# B3606.net
KiCad netlist of a schematic drawn in EAGLE
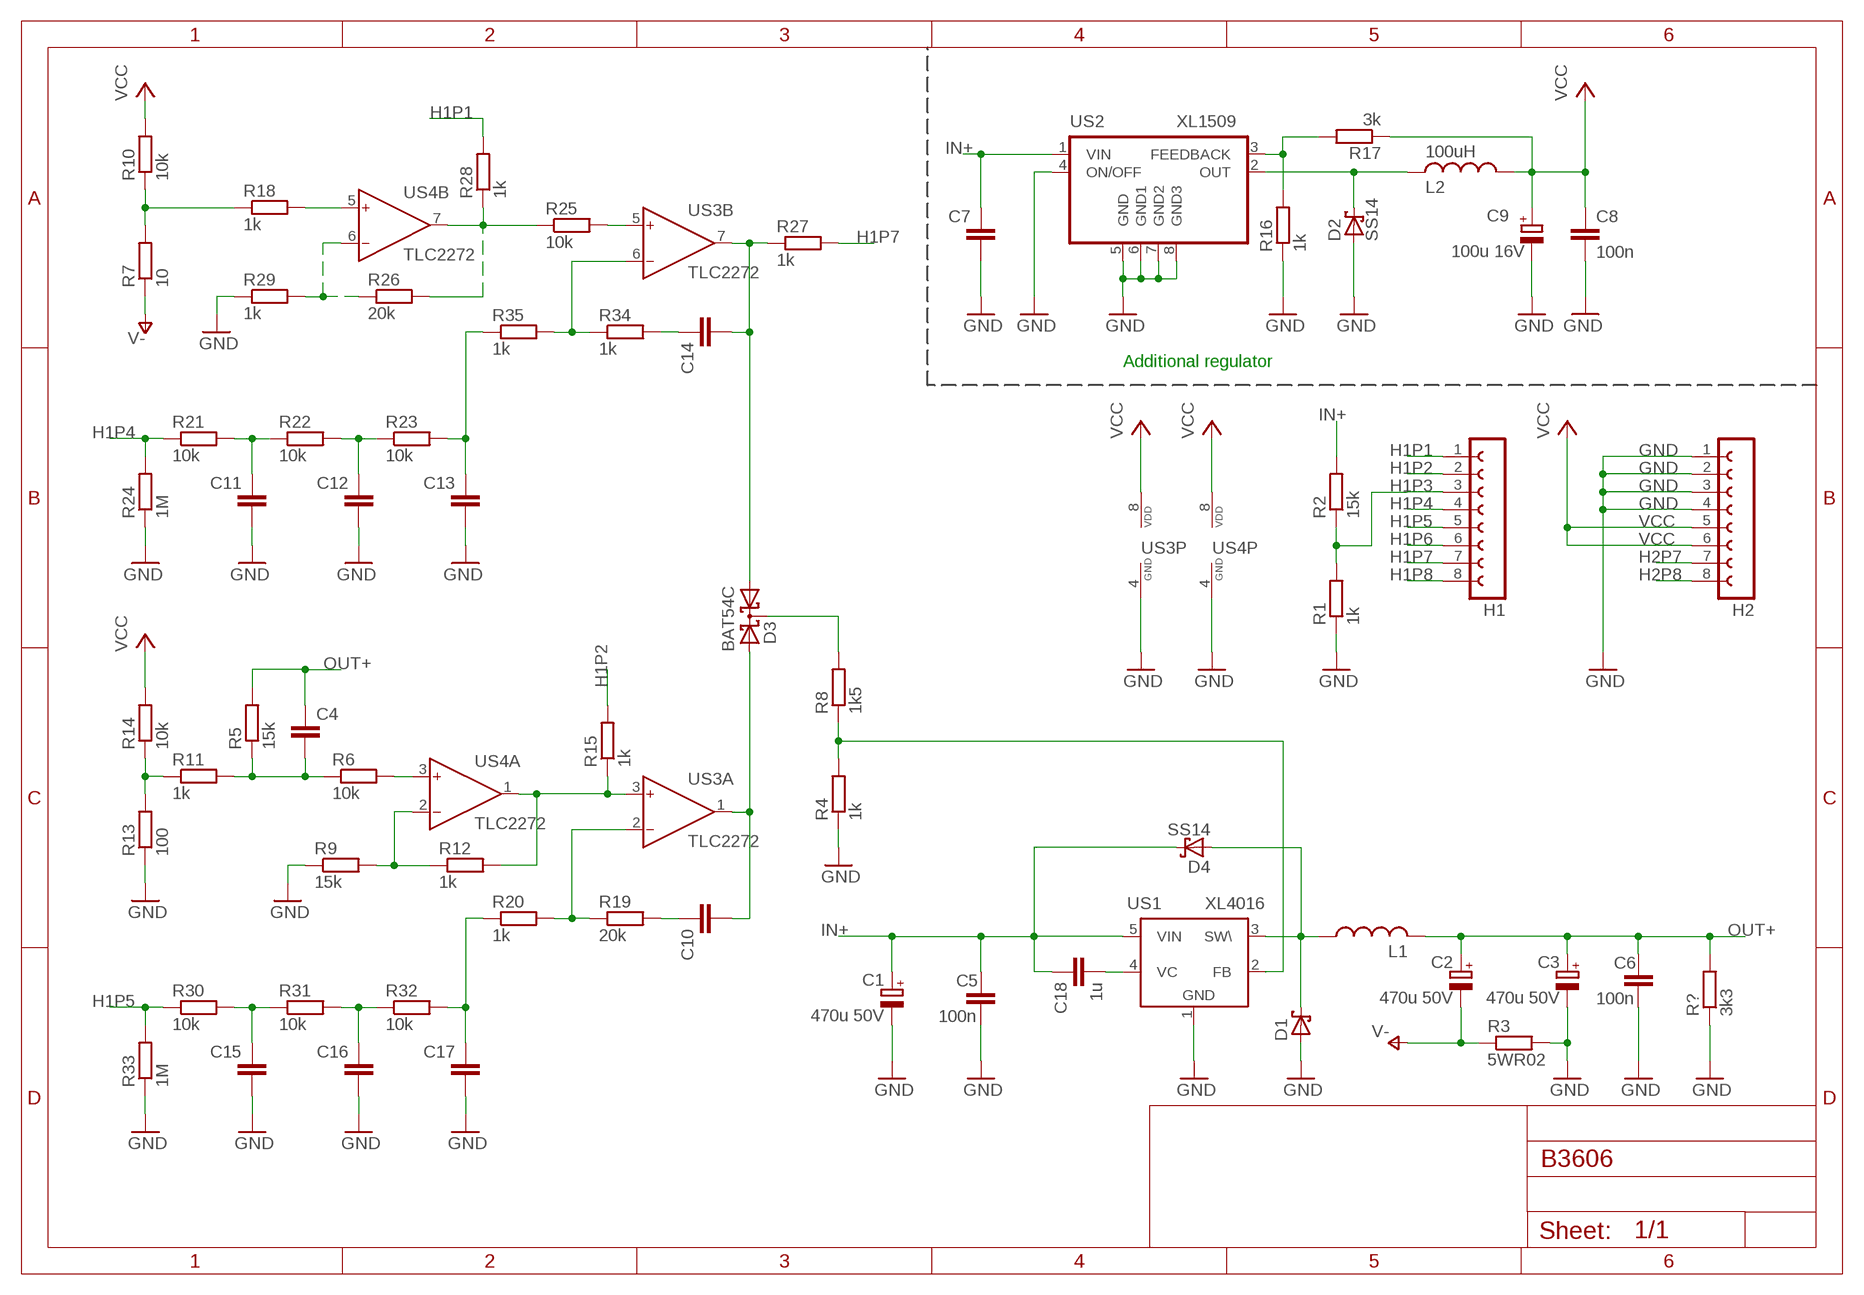
[diagram p0: schematic, sheet 1]

(export (version "E")
  (design (tool "Eeschema 10.0.6"))
  (components
    (comp (ref "C1")
      (value "470u 50V")
      (footprint "eagle-import:E2,5-7")
      (libsource (lib "eagle-import") (part "CPOL-EUE2.5-7"))
    )
    (comp (ref "C2")
      (value "470u 50V")
      (footprint "eagle-import:E2,5-7")
      (libsource (lib "eagle-import") (part "CPOL-EUE2.5-7"))
    )
    (comp (ref "C3")
      (value "470u 50V")
      (footprint "eagle-import:E2,5-7")
      (libsource (lib "eagle-import") (part "CPOL-EUE2.5-7"))
    )
    (comp (ref "C4")
      (value "C-EU025-025X050")
      (footprint "eagle-import:C025-025X050")
      (libsource (lib "eagle-import") (part "C-EU025-025X050"))
    )
    (comp (ref "C5")
      (value "100n")
      (footprint "eagle-import:C025-025X050")
      (libsource (lib "eagle-import") (part "C-EU025-025X050"))
    )
    (comp (ref "C6")
      (value "100n")
      (footprint "eagle-import:C025-025X050")
      (libsource (lib "eagle-import") (part "C-EU025-025X050"))
    )
    (comp (ref "C7")
      (value "C-EUC2012")
      (footprint "eagle-import:C2012")
      (libsource (lib "eagle-import") (part "C-EUC2012"))
    )
    (comp (ref "C8")
      (value "100n")
      (footprint "eagle-import:C025-025X050")
      (libsource (lib "eagle-import") (part "C-EU025-025X050"))
    )
    (comp (ref "C9")
      (value "100u 16V")
      (footprint "eagle-import:E2,5-7")
      (libsource (lib "eagle-import") (part "CPOL-EUE2.5-7"))
    )
    (comp (ref "C10")
      (value "C-EUC2012")
      (footprint "eagle-import:C2012")
      (libsource (lib "eagle-import") (part "C-EUC2012"))
    )
    (comp (ref "C11")
      (value "C-EUC2012")
      (footprint "eagle-import:C2012")
      (libsource (lib "eagle-import") (part "C-EUC2012"))
    )
    (comp (ref "C12")
      (value "C-EUC2012")
      (footprint "eagle-import:C2012")
      (libsource (lib "eagle-import") (part "C-EUC2012"))
    )
    (comp (ref "C13")
      (value "C-EUC2012")
      (footprint "eagle-import:C2012")
      (libsource (lib "eagle-import") (part "C-EUC2012"))
    )
    (comp (ref "C14")
      (value "C-EUC2012")
      (footprint "eagle-import:C2012")
      (libsource (lib "eagle-import") (part "C-EUC2012"))
    )
    (comp (ref "C15")
      (value "C-EUC2012")
      (footprint "eagle-import:C2012")
      (libsource (lib "eagle-import") (part "C-EUC2012"))
    )
    (comp (ref "C16")
      (value "C-EUC2012")
      (footprint "eagle-import:C2012")
      (libsource (lib "eagle-import") (part "C-EUC2012"))
    )
    (comp (ref "C17")
      (value "C-EUC2012")
      (footprint "eagle-import:C2012")
      (libsource (lib "eagle-import") (part "C-EUC2012"))
    )
    (comp (ref "C18")
      (value "1u")
      (footprint "eagle-import:C025-025X050")
      (libsource (lib "eagle-import") (part "C-EU025-025X050"))
    )
    (comp (ref "D1")
      (value "MBR1060")
      (footprint "eagle-import:TO−220AC")
      (libsource (lib "eagle-import") (part "MBR1060"))
    )
    (comp (ref "D2")
      (value "SS14")
      (footprint "eagle-import:DO214AC")
      (libsource (lib "eagle-import") (part "SS14"))
    )
    (comp (ref "D3")
      (value "BAT54C")
      (footprint "eagle-import:SOT23")
      (libsource (lib "eagle-import") (part "BAT54C"))
    )
    (comp (ref "D4")
      (value "SS14")
      (footprint "eagle-import:DO214AC")
      (libsource (lib "eagle-import") (part "SS14"))
    )
    (comp (ref "H1")
      (value "FE08-1")
      (footprint "eagle-import:FE08")
      (libsource (lib "eagle-import") (part "FE08-1"))
    )
    (comp (ref "H2")
      (value "FE08-1")
      (footprint "eagle-import:FE08")
      (libsource (lib "eagle-import") (part "FE08-1"))
    )
    (comp (ref "L1")
      (value "L-USTJ3-U1")
      (footprint "eagle-import:TJ3-U1")
      (libsource (lib "eagle-import") (part "L-USTJ3-U1"))
    )
    (comp (ref "L2")
      (value "100uH")
      (footprint "eagle-import:TJ3-U1")
      (libsource (lib "eagle-import") (part "L-USTJ3-U1"))
    )
    (comp (ref "R1")
      (value "1k")
      (footprint "eagle-import:R2012")
      (libsource (lib "eagle-import") (part "R-EU_R2012"))
    )
    (comp (ref "R2")
      (value "15k")
      (footprint "eagle-import:R2012")
      (libsource (lib "eagle-import") (part "R-EU_R2012"))
    )
    (comp (ref "R3")
      (value "5WR02")
      (footprint "eagle-import:0309_10")
      (libsource (lib "eagle-import") (part "R-EU_0309/10"))
    )
    (comp (ref "R4")
      (value "1k")
      (footprint "eagle-import:R2012")
      (libsource (lib "eagle-import") (part "R-EU_R2012"))
    )
    (comp (ref "R5")
      (value "15k")
      (footprint "eagle-import:0207_10")
      (libsource (lib "eagle-import") (part "R-EU_0207/10"))
    )
    (comp (ref "R6")
      (value "10k")
      (footprint "eagle-import:R2012")
      (libsource (lib "eagle-import") (part "R-EU_R2012"))
    )
    (comp (ref "R7")
      (value "10")
      (footprint "eagle-import:R2012")
      (libsource (lib "eagle-import") (part "R-EU_R2012"))
    )
    (comp (ref "R8")
      (value "1k5")
      (footprint "eagle-import:R2012")
      (libsource (lib "eagle-import") (part "R-EU_R2012"))
    )
    (comp (ref "R9")
      (value "15k")
      (footprint "eagle-import:R2012")
      (libsource (lib "eagle-import") (part "R-EU_R2012"))
    )
    (comp (ref "R10")
      (value "10k")
      (footprint "eagle-import:R2012")
      (libsource (lib "eagle-import") (part "R-EU_R2012"))
    )
    (comp (ref "R11")
      (value "1k")
      (footprint "eagle-import:R2012")
      (libsource (lib "eagle-import") (part "R-EU_R2012"))
    )
    (comp (ref "R12")
      (value "1k")
      (footprint "eagle-import:R2012")
      (libsource (lib "eagle-import") (part "R-EU_R2012"))
    )
    (comp (ref "R13")
      (value "100")
      (footprint "eagle-import:R2012")
      (libsource (lib "eagle-import") (part "R-EU_R2012"))
    )
    (comp (ref "R14")
      (value "10k")
      (footprint "eagle-import:R2012")
      (libsource (lib "eagle-import") (part "R-EU_R2012"))
    )
    (comp (ref "R15")
      (value "1k")
      (footprint "eagle-import:R2012")
      (libsource (lib "eagle-import") (part "R-EU_R2012"))
    )
    (comp (ref "R16")
      (value "1k")
      (footprint "eagle-import:R2012")
      (libsource (lib "eagle-import") (part "R-EU_R2012"))
    )
    (comp (ref "R17")
      (value "3k")
      (footprint "eagle-import:R2012")
      (libsource (lib "eagle-import") (part "R-EU_R2012"))
    )
    (comp (ref "R18")
      (value "1k")
      (footprint "eagle-import:R2012")
      (libsource (lib "eagle-import") (part "R-EU_R2012"))
    )
    (comp (ref "R19")
      (value "20k")
      (footprint "eagle-import:R2012")
      (libsource (lib "eagle-import") (part "R-EU_R2012"))
    )
    (comp (ref "R20")
      (value "1k")
      (footprint "eagle-import:R2012")
      (libsource (lib "eagle-import") (part "R-EU_R2012"))
    )
    (comp (ref "R21")
      (value "10k")
      (footprint "eagle-import:R2012")
      (libsource (lib "eagle-import") (part "R-EU_R2012"))
    )
    (comp (ref "R22")
      (value "10k")
      (footprint "eagle-import:R2012")
      (libsource (lib "eagle-import") (part "R-EU_R2012"))
    )
    (comp (ref "R23")
      (value "10k")
      (footprint "eagle-import:R2012")
      (libsource (lib "eagle-import") (part "R-EU_R2012"))
    )
    (comp (ref "R24")
      (value "1M")
      (footprint "eagle-import:R2012")
      (libsource (lib "eagle-import") (part "R-EU_R2012"))
    )
    (comp (ref "R25")
      (value "10k")
      (footprint "eagle-import:R2012")
      (libsource (lib "eagle-import") (part "R-EU_R2012"))
    )
    (comp (ref "R26")
      (value "20k")
      (footprint "eagle-import:R2012")
      (libsource (lib "eagle-import") (part "R-EU_R2012"))
    )
    (comp (ref "R27")
      (value "1k")
      (footprint "eagle-import:R2012")
      (libsource (lib "eagle-import") (part "R-EU_R2012"))
    )
    (comp (ref "R28")
      (value "1k")
      (footprint "eagle-import:R2012")
      (libsource (lib "eagle-import") (part "R-EU_R2012"))
    )
    (comp (ref "R29")
      (value "1k")
      (footprint "eagle-import:R2012")
      (libsource (lib "eagle-import") (part "R-EU_R2012"))
    )
    (comp (ref "R30")
      (value "10k")
      (footprint "eagle-import:R2012")
      (libsource (lib "eagle-import") (part "R-EU_R2012"))
    )
    (comp (ref "R31")
      (value "10k")
      (footprint "eagle-import:R2012")
      (libsource (lib "eagle-import") (part "R-EU_R2012"))
    )
    (comp (ref "R32")
      (value "10k")
      (footprint "eagle-import:R2012")
      (libsource (lib "eagle-import") (part "R-EU_R2012"))
    )
    (comp (ref "R33")
      (value "1M")
      (footprint "eagle-import:R2012")
      (libsource (lib "eagle-import") (part "R-EU_R2012"))
    )
    (comp (ref "R34")
      (value "1k")
      (footprint "eagle-import:R2012")
      (libsource (lib "eagle-import") (part "R-EU_R2012"))
    )
    (comp (ref "R35")
      (value "1k")
      (footprint "eagle-import:R2012")
      (libsource (lib "eagle-import") (part "R-EU_R2012"))
    )
    (comp (ref "R?")
      (value "3k3")
      (footprint "eagle-import:0207_10")
      (libsource (lib "eagle-import") (part "R-EU_0207/10"))
    )
    (comp (ref "US1")
      (value "XL4016")
      (footprint "eagle-import:TO220-5L")
      (libsource (lib "eagle-import") (part "XL4016"))
    )
    (comp (ref "US2")
      (value "XL1509")
      (footprint "eagle-import:SOP-08")
      (libsource (lib "eagle-import") (part "XL1509"))
    )
    (comp (ref "US3")
      (value "TLC2272")
      (footprint "eagle-import:SOP-08")
      (libsource (lib "eagle-import") (part "TLC2272"))
    )
    (comp (ref "US4")
      (value "TLC2272")
      (footprint "eagle-import:SOP-08")
      (libsource (lib "eagle-import") (part "TLC2272"))
    )
  )
  (nets
    (net (code "1") (name "/H1P1") (class "Default")
      (node (ref "H1") (pin "1") (pinfunction "1_1") (pintype "passive"))
      (node (ref "R28") (pin "2") (pinfunction "2_2") (pintype "passive"))
    )
    (net (code "2") (name "/H1P2") (class "Default")
      (node (ref "H1") (pin "2") (pinfunction "2_2") (pintype "passive"))
      (node (ref "R15") (pin "2") (pinfunction "2_2") (pintype "passive"))
    )
    (net (code "3") (name "/H1P3") (class "Default")
      (node (ref "H1") (pin "3") (pinfunction "3_3") (pintype "passive"))
      (node (ref "R1") (pin "2") (pinfunction "2_2") (pintype "passive"))
      (node (ref "R2") (pin "1") (pinfunction "1_1") (pintype "passive"))
    )
    (net (code "4") (name "/H1P4") (class "Default")
      (node (ref "H1") (pin "4") (pinfunction "4_4") (pintype "passive"))
      (node (ref "R21") (pin "1") (pinfunction "1_1") (pintype "passive"))
      (node (ref "R24") (pin "2") (pinfunction "2_2") (pintype "passive"))
    )
    (net (code "5") (name "/H1P5") (class "Default")
      (node (ref "H1") (pin "5") (pinfunction "5_5") (pintype "passive"))
      (node (ref "R30") (pin "1") (pinfunction "1_1") (pintype "passive"))
      (node (ref "R33") (pin "2") (pinfunction "2_2") (pintype "passive"))
    )
    (net (code "6") (name "/H1P6") (class "Default")
      (node (ref "H1") (pin "6") (pinfunction "6_6") (pintype "passive"))
    )
    (net (code "7") (name "/H1P7") (class "Default")
      (node (ref "H1") (pin "7") (pinfunction "7_7") (pintype "passive"))
      (node (ref "R27") (pin "2") (pinfunction "2_2") (pintype "passive"))
    )
    (net (code "8") (name "/H1P8") (class "Default")
      (node (ref "H1") (pin "8") (pinfunction "8_8") (pintype "passive"))
    )
    (net (code "9") (name "/H2P7") (class "Default")
      (node (ref "H2") (pin "7") (pinfunction "7_7") (pintype "passive"))
    )
    (net (code "10") (name "/H2P8") (class "Default")
      (node (ref "H2") (pin "8") (pinfunction "8_8") (pintype "passive"))
    )
    (net (code "11") (name "/IN+") (class "Default")
      (node (ref "C1") (pin "+") (pinfunction "+_+") (pintype "passive"))
      (node (ref "C18") (pin "1") (pinfunction "1_1") (pintype "passive"))
      (node (ref "C5") (pin "1") (pinfunction "1_1") (pintype "passive"))
      (node (ref "C7") (pin "1") (pinfunction "1_1") (pintype "passive"))
      (node (ref "D4") (pin "C") (pinfunction "C_C") (pintype "passive"))
      (node (ref "R2") (pin "2") (pinfunction "2_2") (pintype "passive"))
      (node (ref "US2") (pin "1") (pinfunction "VIN_1") (pintype "input"))
    )
    (net (code "12") (name "/OUT+") (class "Default")
      (node (ref "C2") (pin "+") (pinfunction "+_+") (pintype "passive"))
      (node (ref "C3") (pin "+") (pinfunction "+_+") (pintype "passive"))
      (node (ref "C4") (pin "1") (pinfunction "1_1") (pintype "passive"))
      (node (ref "C6") (pin "1") (pinfunction "1_1") (pintype "passive"))
      (node (ref "L1") (pin "2") (pinfunction "2_2") (pintype "passive"))
      (node (ref "R5") (pin "2") (pinfunction "2_2") (pintype "passive"))
      (node (ref "R?") (pin "2") (pinfunction "2_2") (pintype "passive"))
    )
    (net (code "13") (name "GND") (class "Default")
      (node (ref "C1") (pin "-") (pinfunction "-_-") (pintype "passive"))
      (node (ref "C11") (pin "2") (pinfunction "2_2") (pintype "passive"))
      (node (ref "C12") (pin "2") (pinfunction "2_2") (pintype "passive"))
      (node (ref "C13") (pin "2") (pinfunction "2_2") (pintype "passive"))
      (node (ref "C15") (pin "2") (pinfunction "2_2") (pintype "passive"))
      (node (ref "C16") (pin "2") (pinfunction "2_2") (pintype "passive"))
      (node (ref "C17") (pin "2") (pinfunction "2_2") (pintype "passive"))
      (node (ref "C3") (pin "-") (pinfunction "-_-") (pintype "passive"))
      (node (ref "C5") (pin "2") (pinfunction "2_2") (pintype "passive"))
      (node (ref "C6") (pin "2") (pinfunction "2_2") (pintype "passive"))
      (node (ref "C7") (pin "2") (pinfunction "2_2") (pintype "passive"))
      (node (ref "C8") (pin "2") (pinfunction "2_2") (pintype "passive"))
      (node (ref "C9") (pin "-") (pinfunction "-_-") (pintype "passive"))
      (node (ref "D1") (pin "A") (pinfunction "A_A") (pintype "passive"))
      (node (ref "D2") (pin "A") (pinfunction "A_A") (pintype "passive"))
      (node (ref "H2") (pin "1") (pinfunction "1_1") (pintype "passive"))
      (node (ref "H2") (pin "2") (pinfunction "2_2") (pintype "passive"))
      (node (ref "H2") (pin "3") (pinfunction "3_3") (pintype "passive"))
      (node (ref "H2") (pin "4") (pinfunction "4_4") (pintype "passive"))
      (node (ref "R1") (pin "1") (pinfunction "1_1") (pintype "passive"))
      (node (ref "R13") (pin "1") (pinfunction "1_1") (pintype "passive"))
      (node (ref "R16") (pin "1") (pinfunction "1_1") (pintype "passive"))
      (node (ref "R24") (pin "1") (pinfunction "1_1") (pintype "passive"))
      (node (ref "R29") (pin "1") (pinfunction "1_1") (pintype "passive"))
      (node (ref "R3") (pin "2") (pinfunction "2_2") (pintype "passive"))
      (node (ref "R33") (pin "1") (pinfunction "1_1") (pintype "passive"))
      (node (ref "R4") (pin "1") (pinfunction "1_1") (pintype "passive"))
      (node (ref "R9") (pin "1") (pinfunction "1_1") (pintype "passive"))
      (node (ref "R?") (pin "1") (pinfunction "1_1") (pintype "passive"))
      (node (ref "US1") (pin "1") (pinfunction "GND_1") (pintype "power_in"))
      (node (ref "US2") (pin "4") (pinfunction "ON/OFF_4") (pintype "power_in"))
      (node (ref "US2") (pin "5") (pinfunction "GND_5") (pintype "power_in"))
      (node (ref "US2") (pin "6") (pinfunction "GND1_6") (pintype "input"))
      (node (ref "US2") (pin "7") (pinfunction "GND2_7") (pintype "output"))
      (node (ref "US2") (pin "8") (pinfunction "GND3_8") (pintype "output"))
      (node (ref "US3") (pin "4") (pinfunction "GND_4") (pintype "power_in"))
      (node (ref "US4") (pin "4") (pinfunction "GND_4") (pintype "power_in"))
    )
    (net (code "14") (name "Net-(C4-Pad2)") (class "Default")
      (node (ref "C4") (pin "2") (pinfunction "2_2") (pintype "passive"))
      (node (ref "R11") (pin "2") (pinfunction "2_2") (pintype "passive"))
      (node (ref "R5") (pin "1") (pinfunction "1_1") (pintype "passive"))
      (node (ref "R6") (pin "1") (pinfunction "1_1") (pintype "passive"))
    )
    (net (code "15") (name "Net-(C10-Pad1)") (class "Default")
      (node (ref "C10") (pin "1") (pinfunction "1_1") (pintype "passive"))
      (node (ref "R19") (pin "2") (pinfunction "2_2") (pintype "passive"))
    )
    (net (code "16") (name "Net-(C11-Pad1)") (class "Default")
      (node (ref "C11") (pin "1") (pinfunction "1_1") (pintype "passive"))
      (node (ref "R21") (pin "2") (pinfunction "2_2") (pintype "passive"))
      (node (ref "R22") (pin "1") (pinfunction "1_1") (pintype "passive"))
    )
    (net (code "17") (name "Net-(C12-Pad1)") (class "Default")
      (node (ref "C12") (pin "1") (pinfunction "1_1") (pintype "passive"))
      (node (ref "R22") (pin "2") (pinfunction "2_2") (pintype "passive"))
      (node (ref "R23") (pin "1") (pinfunction "1_1") (pintype "passive"))
    )
    (net (code "18") (name "Net-(C13-Pad1)") (class "Default")
      (node (ref "C13") (pin "1") (pinfunction "1_1") (pintype "passive"))
      (node (ref "R23") (pin "2") (pinfunction "2_2") (pintype "passive"))
      (node (ref "R35") (pin "1") (pinfunction "1_1") (pintype "passive"))
    )
    (net (code "19") (name "Net-(C14-Pad1)") (class "Default")
      (node (ref "C14") (pin "1") (pinfunction "1_1") (pintype "passive"))
      (node (ref "R34") (pin "2") (pinfunction "2_2") (pintype "passive"))
    )
    (net (code "20") (name "Net-(C15-Pad1)") (class "Default")
      (node (ref "C15") (pin "1") (pinfunction "1_1") (pintype "passive"))
      (node (ref "R30") (pin "2") (pinfunction "2_2") (pintype "passive"))
      (node (ref "R31") (pin "1") (pinfunction "1_1") (pintype "passive"))
    )
    (net (code "21") (name "Net-(C16-Pad1)") (class "Default")
      (node (ref "C16") (pin "1") (pinfunction "1_1") (pintype "passive"))
      (node (ref "R31") (pin "2") (pinfunction "2_2") (pintype "passive"))
      (node (ref "R32") (pin "1") (pinfunction "1_1") (pintype "passive"))
    )
    (net (code "22") (name "Net-(C17-Pad1)") (class "Default")
      (node (ref "C17") (pin "1") (pinfunction "1_1") (pintype "passive"))
      (node (ref "R20") (pin "1") (pinfunction "1_1") (pintype "passive"))
      (node (ref "R32") (pin "2") (pinfunction "2_2") (pintype "passive"))
    )
    (net (code "23") (name "Net-(D1-PadC)") (class "Default")
      (node (ref "D1") (pin "C") (pinfunction "C_C") (pintype "passive"))
      (node (ref "D4") (pin "A") (pinfunction "A_A") (pintype "passive"))
      (node (ref "L1") (pin "1") (pinfunction "1_1") (pintype "passive"))
    )
    (net (code "24") (name "Net-(D3-A1)") (class "Default")
      (node (ref "C14") (pin "2") (pinfunction "2_2") (pintype "passive"))
      (node (ref "D3") (pin "1") (pinfunction "A1_1") (pintype "passive"))
      (node (ref "R27") (pin "1") (pinfunction "1_1") (pintype "passive"))
      (node (ref "US3") (pin "7") (pinfunction "2OUT_7") (pintype "output"))
    )
    (net (code "25") (name "Net-(D3-A2)") (class "Default")
      (node (ref "C10") (pin "2") (pinfunction "2_2") (pintype "passive"))
      (node (ref "D3") (pin "2") (pinfunction "A2_2") (pintype "passive"))
      (node (ref "US3") (pin "1") (pinfunction "1OUT_1") (pintype "output"))
    )
    (net (code "26") (name "Net-(D3-CC)") (class "Default")
      (node (ref "D3") (pin "3") (pinfunction "CC_3") (pintype "passive"))
      (node (ref "R8") (pin "2") (pinfunction "2_2") (pintype "passive"))
    )
    (net (code "27") (name "Net-(R10-Pad1)") (class "Default")
      (node (ref "R10") (pin "1") (pinfunction "1_1") (pintype "passive"))
      (node (ref "R18") (pin "1") (pinfunction "1_1") (pintype "passive"))
      (node (ref "R7") (pin "2") (pinfunction "2_2") (pintype "passive"))
    )
    (net (code "28") (name "Net-(R11-Pad1)") (class "Default")
      (node (ref "R11") (pin "1") (pinfunction "1_1") (pintype "passive"))
      (node (ref "R13") (pin "2") (pinfunction "2_2") (pintype "passive"))
      (node (ref "R14") (pin "1") (pinfunction "1_1") (pintype "passive"))
    )
    (net (code "29") (name "Net-(US1-FB)") (class "Default")
      (node (ref "R4") (pin "2") (pinfunction "2_2") (pintype "passive"))
      (node (ref "R8") (pin "1") (pinfunction "1_1") (pintype "passive"))
      (node (ref "US1") (pin "2") (pinfunction "FB_2") (pintype "input"))
    )
    (net (code "30") (name "Net-(US1-VC)") (class "Default")
      (node (ref "C18") (pin "2") (pinfunction "2_2") (pintype "passive"))
      (node (ref "US1") (pin "4") (pinfunction "VC_4") (pintype "input"))
    )
    (net (code "31") (name "Net-(US2-FEEDBACK)") (class "Default")
      (node (ref "R16") (pin "2") (pinfunction "2_2") (pintype "passive"))
      (node (ref "R17") (pin "2") (pinfunction "2_2") (pintype "passive"))
      (node (ref "US2") (pin "3") (pinfunction "FEEDBACK_3") (pintype "input"))
    )
    (net (code "32") (name "Net-(US2-OUT)") (class "Default")
      (node (ref "D2") (pin "C") (pinfunction "C_C") (pintype "passive"))
      (node (ref "L2") (pin "2") (pinfunction "2_2") (pintype "passive"))
      (node (ref "US2") (pin "2") (pinfunction "OUT_2") (pintype "input"))
    )
    (net (code "33") (name "Net-(US3A-1IN+)") (class "Default")
      (node (ref "R12") (pin "2") (pinfunction "2_2") (pintype "passive"))
      (node (ref "R15") (pin "1") (pinfunction "1_1") (pintype "passive"))
      (node (ref "US3") (pin "3") (pinfunction "1IN+_3") (pintype "input"))
      (node (ref "US4") (pin "1") (pinfunction "1OUT_1") (pintype "output"))
    )
    (net (code "34") (name "Net-(US3A-1IN-)") (class "Default")
      (node (ref "R19") (pin "1") (pinfunction "1_1") (pintype "passive"))
      (node (ref "R20") (pin "2") (pinfunction "2_2") (pintype "passive"))
      (node (ref "US3") (pin "2") (pinfunction "1IN-_2") (pintype "input"))
    )
    (net (code "35") (name "Net-(US3B-2IN+)") (class "Default")
      (node (ref "R25") (pin "2") (pinfunction "2_2") (pintype "passive"))
      (node (ref "US3") (pin "5") (pinfunction "2IN+_5") (pintype "input"))
    )
    (net (code "36") (name "Net-(US3B-2IN-)") (class "Default")
      (node (ref "R34") (pin "1") (pinfunction "1_1") (pintype "passive"))
      (node (ref "R35") (pin "2") (pinfunction "2_2") (pintype "passive"))
      (node (ref "US3") (pin "6") (pinfunction "2IN-_6") (pintype "input"))
    )
    (net (code "37") (name "Net-(US4A-1IN+)") (class "Default")
      (node (ref "R6") (pin "2") (pinfunction "2_2") (pintype "passive"))
      (node (ref "US4") (pin "3") (pinfunction "1IN+_3") (pintype "input"))
    )
    (net (code "38") (name "Net-(US4A-1IN-)") (class "Default")
      (node (ref "R12") (pin "1") (pinfunction "1_1") (pintype "passive"))
      (node (ref "R9") (pin "2") (pinfunction "2_2") (pintype "passive"))
      (node (ref "US4") (pin "2") (pinfunction "1IN-_2") (pintype "input"))
    )
    (net (code "39") (name "Net-(US4B-2IN+)") (class "Default")
      (node (ref "R18") (pin "2") (pinfunction "2_2") (pintype "passive"))
      (node (ref "US4") (pin "5") (pinfunction "2IN+_5") (pintype "input"))
    )
    (net (code "40") (name "Net-(US4B-2IN-)") (class "Default")
      (node (ref "R26") (pin "1") (pinfunction "1_1") (pintype "passive"))
      (node (ref "R29") (pin "2") (pinfunction "2_2") (pintype "passive"))
      (node (ref "US4") (pin "6") (pinfunction "2IN-_6") (pintype "input"))
    )
    (net (code "41") (name "Net-(US4B-2OUT)") (class "Default")
      (node (ref "R25") (pin "1") (pinfunction "1_1") (pintype "passive"))
      (node (ref "R26") (pin "2") (pinfunction "2_2") (pintype "passive"))
      (node (ref "R28") (pin "1") (pinfunction "1_1") (pintype "passive"))
      (node (ref "US4") (pin "7") (pinfunction "2OUT_7") (pintype "output"))
    )
    (net (code "42") (name "V-") (class "Default")
      (node (ref "C2") (pin "-") (pinfunction "-_-") (pintype "passive"))
      (node (ref "R3") (pin "1") (pinfunction "1_1") (pintype "passive"))
      (node (ref "R7") (pin "1") (pinfunction "1_1") (pintype "passive"))
    )
    (net (code "43") (name "VCC") (class "Default")
      (node (ref "C8") (pin "1") (pinfunction "1_1") (pintype "passive"))
      (node (ref "C9") (pin "+") (pinfunction "+_+") (pintype "passive"))
      (node (ref "H2") (pin "5") (pinfunction "5_5") (pintype "passive"))
      (node (ref "H2") (pin "6") (pinfunction "6_6") (pintype "passive"))
      (node (ref "L2") (pin "1") (pinfunction "1_1") (pintype "passive"))
      (node (ref "R10") (pin "2") (pinfunction "2_2") (pintype "passive"))
      (node (ref "R14") (pin "2") (pinfunction "2_2") (pintype "passive"))
      (node (ref "R17") (pin "1") (pinfunction "1_1") (pintype "passive"))
      (node (ref "US3") (pin "8") (pinfunction "VDD_8") (pintype "power_in"))
      (node (ref "US4") (pin "8") (pinfunction "VDD_8") (pintype "power_in"))
    )
    (net (code "44") (name "unconnected-(US1-SW\\-Pad3)") (class "Default")
      (node (ref "US1") (pin "3") (pinfunction "SW\\_3") (pintype "output"))
    )
    (net (code "45") (name "unconnected-(US1-VIN-Pad5)") (class "Default")
      (node (ref "US1") (pin "5") (pinfunction "VIN_5") (pintype "input"))
    )
  )
)
